# 2228_Recepteur_PIC32.net
KiCad netlist of a schematic drawn in Altium Designer
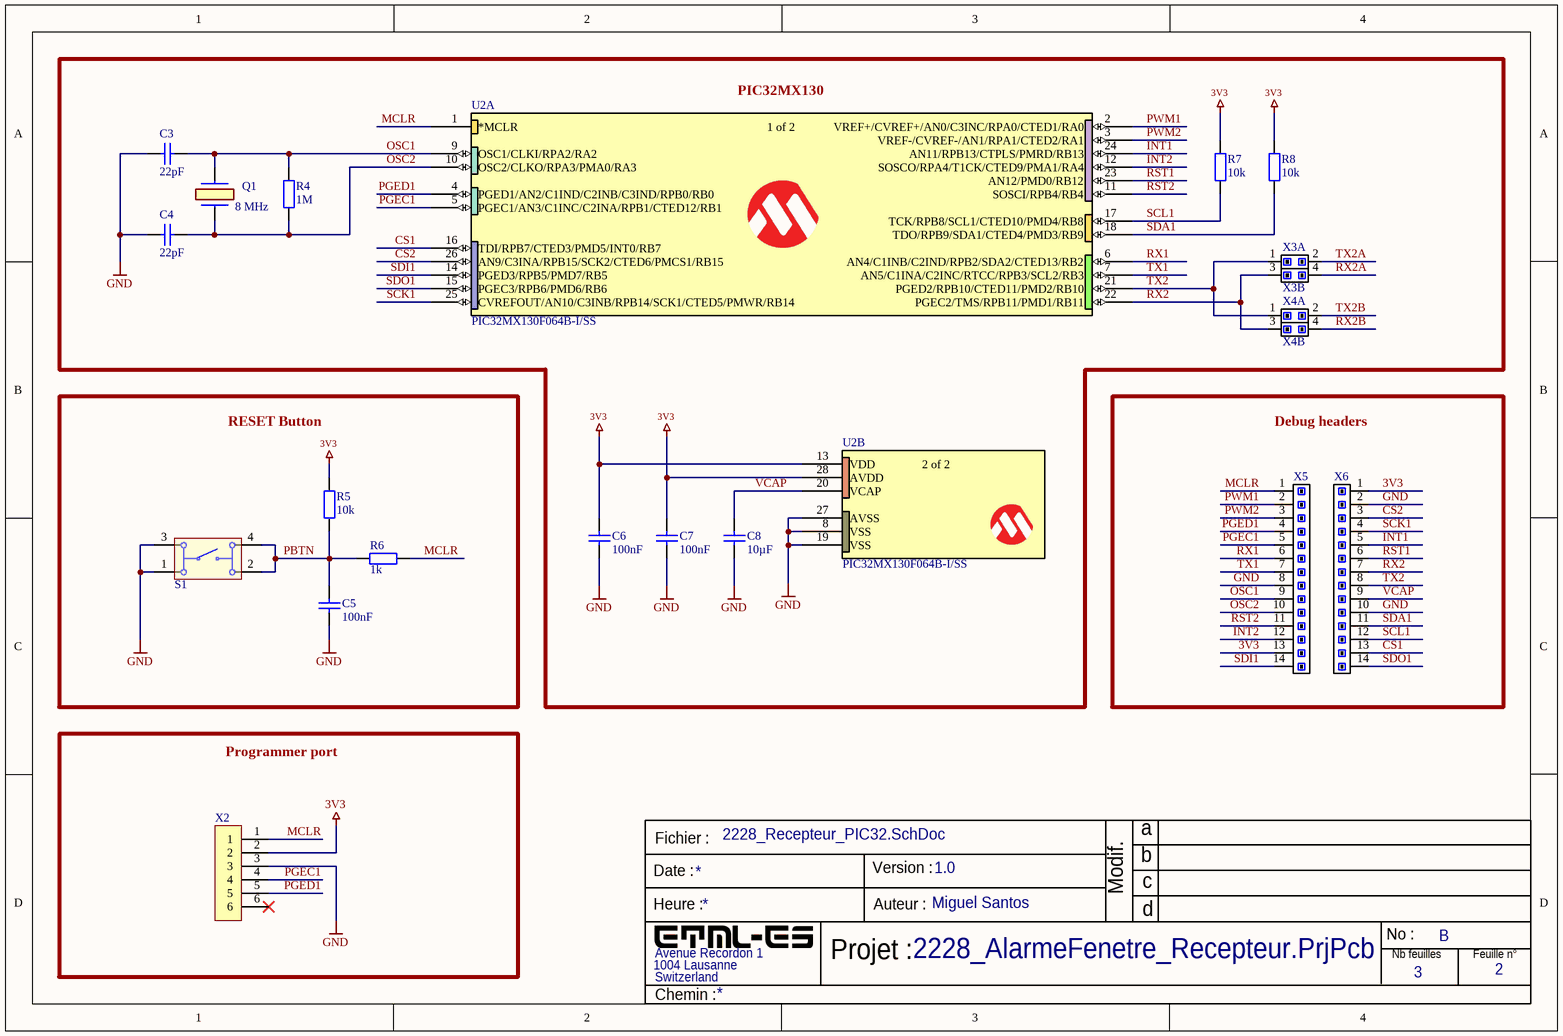
[diagram p0: 2228_Recepteur_PIC32.SchDoc]

(export (version "E")
  (design (tool "Eeschema 10.0.6"))
  (components
    (comp (ref "C3")
      (value "22pF")
      (footprint "CAP_0805")
      (description "Ceramic capacitor")
      (fields (field (name "Comment") "CAP_SMD"))
      (libsource (lib "2228_AlarmeFenetre_Symbols") (part "CAP_SMD"))
    )
    (comp (ref "C4")
      (value "22pF")
      (footprint "CAP_0805")
      (description "Ceramic capacitor")
      (fields (field (name "Comment") "CAP_SMD"))
      (libsource (lib "2228_AlarmeFenetre_Symbols") (part "CAP_SMD"))
    )
    (comp (ref "C5")
      (value "100nF")
      (footprint "CAP_0805")
      (description "Ceramic capacitor")
      (fields (field (name "Comment") "CAP_SMD"))
      (libsource (lib "2228_AlarmeFenetre_Symbols") (part "CAP_SMD"))
    )
    (comp (ref "C6")
      (value "100nF")
      (footprint "CAP_0805")
      (description "Ceramic capacitor")
      (fields (field (name "Comment") "CAP_SMD"))
      (libsource (lib "2228_AlarmeFenetre_Symbols") (part "CAP_SMD"))
    )
    (comp (ref "C7")
      (value "100nF")
      (footprint "CAP_0805")
      (description "Ceramic capacitor")
      (fields (field (name "Comment") "CAP_SMD"))
      (libsource (lib "2228_AlarmeFenetre_Symbols") (part "CAP_SMD"))
    )
    (comp (ref "C8")
      (value "10µF")
      (footprint "CAP_0805")
      (description "Ceramic capacitor")
      (fields (field (name "Comment") "CAP_SMD"))
      (libsource (lib "2228_AlarmeFenetre_Symbols") (part "CAP_SMD"))
    )
    (comp (ref "Q1")
      (value "8 MHz")
      (footprint "LFXTAL003151")
      (description "IQD FREQUENCY PRODUCTS - LFXTAL003151REEL - CRYSTAL, 8MHZ, 16PF, 11.4 X 4.9MM")
      (fields
        (field (name "MANUFACTURER_PART_NUMBER") "LFXTAL003151REEL")
        (field (name "MOUSER PART NUMBER") "449-LFXTAL003151REEL")
      )
      (libsource (lib "2228_AlarmeFenetre_Symbols") (part "LFXTAL003151"))
    )
    (comp (ref "R4")
      (value "1M")
      (footprint "RES_0805")
      (fields (field (name "Comment") "RES_SMD"))
      (libsource (lib "2228_AlarmeFenetre_Symbols") (part "RES_SMD"))
    )
    (comp (ref "R5")
      (value "10k")
      (footprint "RES_0805")
      (fields (field (name "Comment") "RES_SMD"))
      (libsource (lib "2228_AlarmeFenetre_Symbols") (part "RES_SMD"))
    )
    (comp (ref "R6")
      (value "1k")
      (footprint "RES_0805")
      (fields (field (name "Comment") "RES_SMD"))
      (libsource (lib "") (part "RES_SMD_1"))
    )
    (comp (ref "R7")
      (value "10k")
      (footprint "RES_0805")
      (fields (field (name "Comment") "RES_SMD"))
      (libsource (lib "2228_AlarmeFenetre_Symbols") (part "RES_SMD"))
    )
    (comp (ref "R8")
      (value "10k")
      (footprint "RES_0805")
      (fields (field (name "Comment") "RES_SMD"))
      (libsource (lib "2228_AlarmeFenetre_Symbols") (part "RES_SMD"))
    )
    (comp (ref "S1")
      (value "430182043816")
      (footprint "430182043816")
      (description "WS-TASV SMD Tact Switch 6X6 mm")
      (fields (field (name "MANUFACTURER") "Wuerth Elektronik"))
      (libsource (lib "Altium Content Vault") (part "WE-TACT-SW-4"))
    )
    (comp (ref "U2")
      (value "PIC32MX130F064B-I/SS")
      (footprint "2228_AlarmeFenetre_Footprints:SSOP28_MC_MCH-M")
      (fields (field (name "MANUFACTURER") "Microchip"))
      (libsource (lib "2228_AlarmeFenetre_Symbols") (part "PIC32MX130F064B-I/SS"))
    )
    (comp (ref "X2")
      (value "6 pins Header")
      (footprint "HEADER_6PINS")
      (libsource (lib "2209_CommandeDomotiqueIR") (part "6 pins Header"))
    )
    (comp (ref "X3")
      (value "2X2PIN_HEADER")
      (footprint "2x2_HEADER")
      (libsource (lib "2228_AlarmeFenetre_Symbols") (part "2X2PIN_HEADER"))
    )
    (comp (ref "X4")
      (value "2X2PIN_HEADER")
      (footprint "2x2_HEADER")
      (libsource (lib "2228_AlarmeFenetre_Symbols") (part "2X2PIN_HEADER"))
    )
    (comp (ref "X5")
      (value "14PIN_HEADER")
      (footprint "HEADER_14PINS")
      (libsource (lib "") (part "14PIN_HEADER_1"))
    )
    (comp (ref "X6")
      (value "14PIN_HEADER")
      (footprint "HEADER_14PINS")
      (libsource (lib "2228_AlarmeFenetre_Symbols") (part "14PIN_HEADER"))
    )
  )
  (nets
    (net (code "1") (name "/CS1") (class "Default")
      (node (ref "U2") (pin "16") (pinfunction "TDI/RPB7/CTED3/PMD5/INT0/RB7_16") (pintype "bidirectional"))
      (node (ref "X6") (pin "13") (pinfunction "13_13") (pintype "passive"))
    )
    (net (code "2") (name "/CS2") (class "Default")
      (node (ref "U2") (pin "26") (pinfunction "AN9/C3INA/RPB15/SCK2/CTED6/PMCS1/RB15_26") (pintype "bidirectional"))
      (node (ref "X6") (pin "3") (pinfunction "3_3") (pintype "passive"))
    )
    (net (code "3") (name "/INT1") (class "Default")
      (node (ref "U2") (pin "24") (pinfunction "AN11/RPB13/CTPLS/PMRD/RB13_24") (pintype "bidirectional"))
      (node (ref "X6") (pin "5") (pinfunction "5_5") (pintype "passive"))
    )
    (net (code "4") (name "/INT2") (class "Default")
      (node (ref "U2") (pin "12") (pinfunction "SOSCO/RPA4/T1CK/CTED9/PMA1/RA4_12") (pintype "bidirectional"))
      (node (ref "X5") (pin "12") (pinfunction "12_12") (pintype "passive"))
    )
    (net (code "5") (name "/MCLR") (class "Default")
      (node (ref "R6") (pin "1") (pinfunction "1_1") (pintype "passive"))
      (node (ref "U2") (pin "1") (pinfunction "*MCLR_1") (pintype "passive"))
      (node (ref "X2") (pin "1") (pinfunction "1_1") (pintype "passive"))
      (node (ref "X5") (pin "1") (pinfunction "1_1") (pintype "passive"))
    )
    (net (code "6") (name "/OSC1") (class "Default")
      (node (ref "C3") (pin "1") (pinfunction "1_1") (pintype "passive"))
      (node (ref "Q1") (pin "1") (pinfunction "1_1") (pintype "passive"))
      (node (ref "R4") (pin "2") (pinfunction "2_2") (pintype "passive"))
      (node (ref "U2") (pin "9") (pinfunction "OSC1/CLKI/RPA2/RA2_9") (pintype "bidirectional"))
      (node (ref "X5") (pin "9") (pinfunction "9_9") (pintype "passive"))
    )
    (net (code "7") (name "/OSC2") (class "Default")
      (node (ref "C4") (pin "2") (pinfunction "2_2") (pintype "passive"))
      (node (ref "Q1") (pin "2") (pinfunction "2_2") (pintype "passive"))
      (node (ref "R4") (pin "1") (pinfunction "1_1") (pintype "passive"))
      (node (ref "U2") (pin "10") (pinfunction "OSC2/CLKO/RPA3/PMA0/RA3_10") (pintype "bidirectional"))
      (node (ref "X5") (pin "10") (pinfunction "10_10") (pintype "passive"))
    )
    (net (code "8") (name "/PBTN") (class "Default")
      (node (ref "C5") (pin "1") (pinfunction "1_1") (pintype "passive"))
      (node (ref "R5") (pin "1") (pinfunction "1_1") (pintype "passive"))
      (node (ref "R6") (pin "2") (pinfunction "2_2") (pintype "passive"))
      (node (ref "S1") (pin "2") (pinfunction "2_2") (pintype "passive"))
      (node (ref "S1") (pin "4") (pinfunction "4_4") (pintype "passive"))
    )
    (net (code "9") (name "/PGEC1") (class "Default")
      (node (ref "U2") (pin "5") (pinfunction "PGEC1/AN3/C1INC/C2INA/RPB1/CTED12/RB1_5") (pintype "bidirectional"))
      (node (ref "X2") (pin "4") (pinfunction "4_4") (pintype "passive"))
      (node (ref "X5") (pin "5") (pinfunction "5_5") (pintype "passive"))
    )
    (net (code "10") (name "/PGED1") (class "Default")
      (node (ref "U2") (pin "4") (pinfunction "PGED1/AN2/C1IND/C2INB/C3IND/RPB0/RB0_4") (pintype "bidirectional"))
      (node (ref "X2") (pin "5") (pinfunction "5_5") (pintype "passive"))
      (node (ref "X5") (pin "4") (pinfunction "4_4") (pintype "passive"))
    )
    (net (code "11") (name "/PWM1") (class "Default")
      (node (ref "U2") (pin "2") (pinfunction "VREF+/CVREF+/AN0/C3INC/RPA0/CTED1/RA0_2") (pintype "bidirectional"))
      (node (ref "X5") (pin "2") (pinfunction "2_2") (pintype "passive"))
    )
    (net (code "12") (name "/PWM2") (class "Default")
      (node (ref "U2") (pin "3") (pinfunction "VREF-/CVREF-/AN1/RPA1/CTED2/RA1_3") (pintype "bidirectional"))
      (node (ref "X5") (pin "3") (pinfunction "3_3") (pintype "passive"))
    )
    (net (code "13") (name "/RST1") (class "Default")
      (node (ref "U2") (pin "23") (pinfunction "AN12/PMD0/RB12_23") (pintype "bidirectional"))
      (node (ref "X6") (pin "6") (pinfunction "6_6") (pintype "passive"))
    )
    (net (code "14") (name "/RST2") (class "Default")
      (node (ref "U2") (pin "11") (pinfunction "SOSCI/RPB4/RB4_11") (pintype "bidirectional"))
      (node (ref "X5") (pin "11") (pinfunction "11_11") (pintype "passive"))
    )
    (net (code "15") (name "/RX1") (class "Default")
      (node (ref "U2") (pin "6") (pinfunction "AN4/C1INB/C2IND/RPB2/SDA2/CTED13/RB2_6") (pintype "bidirectional"))
      (node (ref "X5") (pin "6") (pinfunction "6_6") (pintype "passive"))
    )
    (net (code "16") (name "/RX2") (class "Default")
      (node (ref "U2") (pin "22") (pinfunction "PGEC2/TMS/RPB11/PMD1/RB11_22") (pintype "bidirectional"))
      (node (ref "X3") (pin "3") (pinfunction "3_3") (pintype "passive"))
      (node (ref "X4") (pin "3") (pinfunction "3_3") (pintype "passive"))
      (node (ref "X6") (pin "7") (pinfunction "7_7") (pintype "passive"))
    )
    (net (code "17") (name "/RX2A") (class "Default")
      (node (ref "X3") (pin "4") (pinfunction "4_4") (pintype "passive"))
    )
    (net (code "18") (name "/RX2B") (class "Default")
      (node (ref "X4") (pin "4") (pinfunction "4_4") (pintype "passive"))
    )
    (net (code "19") (name "/SCK1") (class "Default")
      (node (ref "U2") (pin "25") (pinfunction "CVREFOUT/AN10/C3INB/RPB14/SCK1/CTED5/PMWR/RB14_25") (pintype "bidirectional"))
      (node (ref "X6") (pin "4") (pinfunction "4_4") (pintype "passive"))
    )
    (net (code "20") (name "/SCL1") (class "Default")
      (node (ref "R7") (pin "1") (pinfunction "1_1") (pintype "passive"))
      (node (ref "U2") (pin "17") (pinfunction "TCK/RPB8/SCL1/CTED10/PMD4/RB8_17") (pintype "bidirectional"))
      (node (ref "X6") (pin "12") (pinfunction "12_12") (pintype "passive"))
    )
    (net (code "21") (name "/SDA1") (class "Default")
      (node (ref "R8") (pin "1") (pinfunction "1_1") (pintype "passive"))
      (node (ref "U2") (pin "18") (pinfunction "TDO/RPB9/SDA1/CTED4/PMD3/RB9_18") (pintype "bidirectional"))
      (node (ref "X6") (pin "11") (pinfunction "11_11") (pintype "passive"))
    )
    (net (code "22") (name "/SDI1") (class "Default")
      (node (ref "U2") (pin "14") (pinfunction "PGED3/RPB5/PMD7/RB5_14") (pintype "bidirectional"))
      (node (ref "X5") (pin "14") (pinfunction "14_14") (pintype "passive"))
    )
    (net (code "23") (name "/SDO1") (class "Default")
      (node (ref "U2") (pin "15") (pinfunction "PGEC3/RPB6/PMD6/RB6_15") (pintype "bidirectional"))
      (node (ref "X6") (pin "14") (pinfunction "14_14") (pintype "passive"))
    )
    (net (code "24") (name "/TX1") (class "Default")
      (node (ref "U2") (pin "7") (pinfunction "AN5/C1INA/C2INC/RTCC/RPB3/SCL2/RB3_7") (pintype "bidirectional"))
      (node (ref "X5") (pin "7") (pinfunction "7_7") (pintype "passive"))
    )
    (net (code "25") (name "/TX2") (class "Default")
      (node (ref "U2") (pin "21") (pinfunction "PGED2/RPB10/CTED11/PMD2/RB10_21") (pintype "bidirectional"))
      (node (ref "X3") (pin "1") (pinfunction "1_1") (pintype "passive"))
      (node (ref "X4") (pin "1") (pinfunction "1_1") (pintype "passive"))
      (node (ref "X6") (pin "8") (pinfunction "8_8") (pintype "passive"))
    )
    (net (code "26") (name "/TX2A") (class "Default")
      (node (ref "X3") (pin "2") (pinfunction "2_2") (pintype "passive"))
    )
    (net (code "27") (name "/TX2B") (class "Default")
      (node (ref "X4") (pin "2") (pinfunction "2_2") (pintype "passive"))
    )
    (net (code "28") (name "/VCAP") (class "Default")
      (node (ref "C8") (pin "1") (pinfunction "1_1") (pintype "passive"))
      (node (ref "U2") (pin "20") (pinfunction "VCAP_20") (pintype "power_in"))
      (node (ref "X6") (pin "9") (pinfunction "9_9") (pintype "passive"))
    )
    (net (code "29") (name "3V3") (class "Default")
      (node (ref "C6") (pin "1") (pinfunction "1_1") (pintype "passive"))
      (node (ref "C7") (pin "1") (pinfunction "1_1") (pintype "passive"))
      (node (ref "R5") (pin "2") (pinfunction "2_2") (pintype "passive"))
      (node (ref "R7") (pin "2") (pinfunction "2_2") (pintype "passive"))
      (node (ref "R8") (pin "2") (pinfunction "2_2") (pintype "passive"))
      (node (ref "U2") (pin "13") (pinfunction "VDD_13") (pintype "power_in"))
      (node (ref "U2") (pin "28") (pinfunction "AVDD_28") (pintype "power_in"))
      (node (ref "X2") (pin "2") (pinfunction "2_2") (pintype "passive"))
      (node (ref "X5") (pin "13") (pinfunction "13_13") (pintype "passive"))
      (node (ref "X6") (pin "1") (pinfunction "1_1") (pintype "passive"))
    )
    (net (code "30") (name "GND") (class "Default")
      (node (ref "C3") (pin "2") (pinfunction "2_2") (pintype "passive"))
      (node (ref "C4") (pin "1") (pinfunction "1_1") (pintype "passive"))
      (node (ref "C5") (pin "2") (pinfunction "2_2") (pintype "passive"))
      (node (ref "C6") (pin "2") (pinfunction "2_2") (pintype "passive"))
      (node (ref "C7") (pin "2") (pinfunction "2_2") (pintype "passive"))
      (node (ref "C8") (pin "2") (pinfunction "2_2") (pintype "passive"))
      (node (ref "S1") (pin "1") (pinfunction "1_1") (pintype "passive"))
      (node (ref "S1") (pin "3") (pinfunction "3_3") (pintype "passive"))
      (node (ref "U2") (pin "19") (pinfunction "VSS_19") (pintype "power_in"))
      (node (ref "U2") (pin "27") (pinfunction "AVSS_27") (pintype "power_in"))
      (node (ref "U2") (pin "8") (pinfunction "VSS_8") (pintype "power_in"))
      (node (ref "X2") (pin "3") (pinfunction "3_3") (pintype "passive"))
      (node (ref "X5") (pin "8") (pinfunction "8_8") (pintype "passive"))
      (node (ref "X6") (pin "10") (pinfunction "10_10") (pintype "passive"))
      (node (ref "X6") (pin "2") (pinfunction "2_2") (pintype "passive"))
    )
    (net (code "31") (name "unconnected-(X2-Pad6)") (class "Default")
      (node (ref "X2") (pin "6") (pinfunction "6_6") (pintype "passive+no_connect"))
    )
  )
)
